# MainSheet.net
KiCad netlist of a schematic drawn in Altium Designer
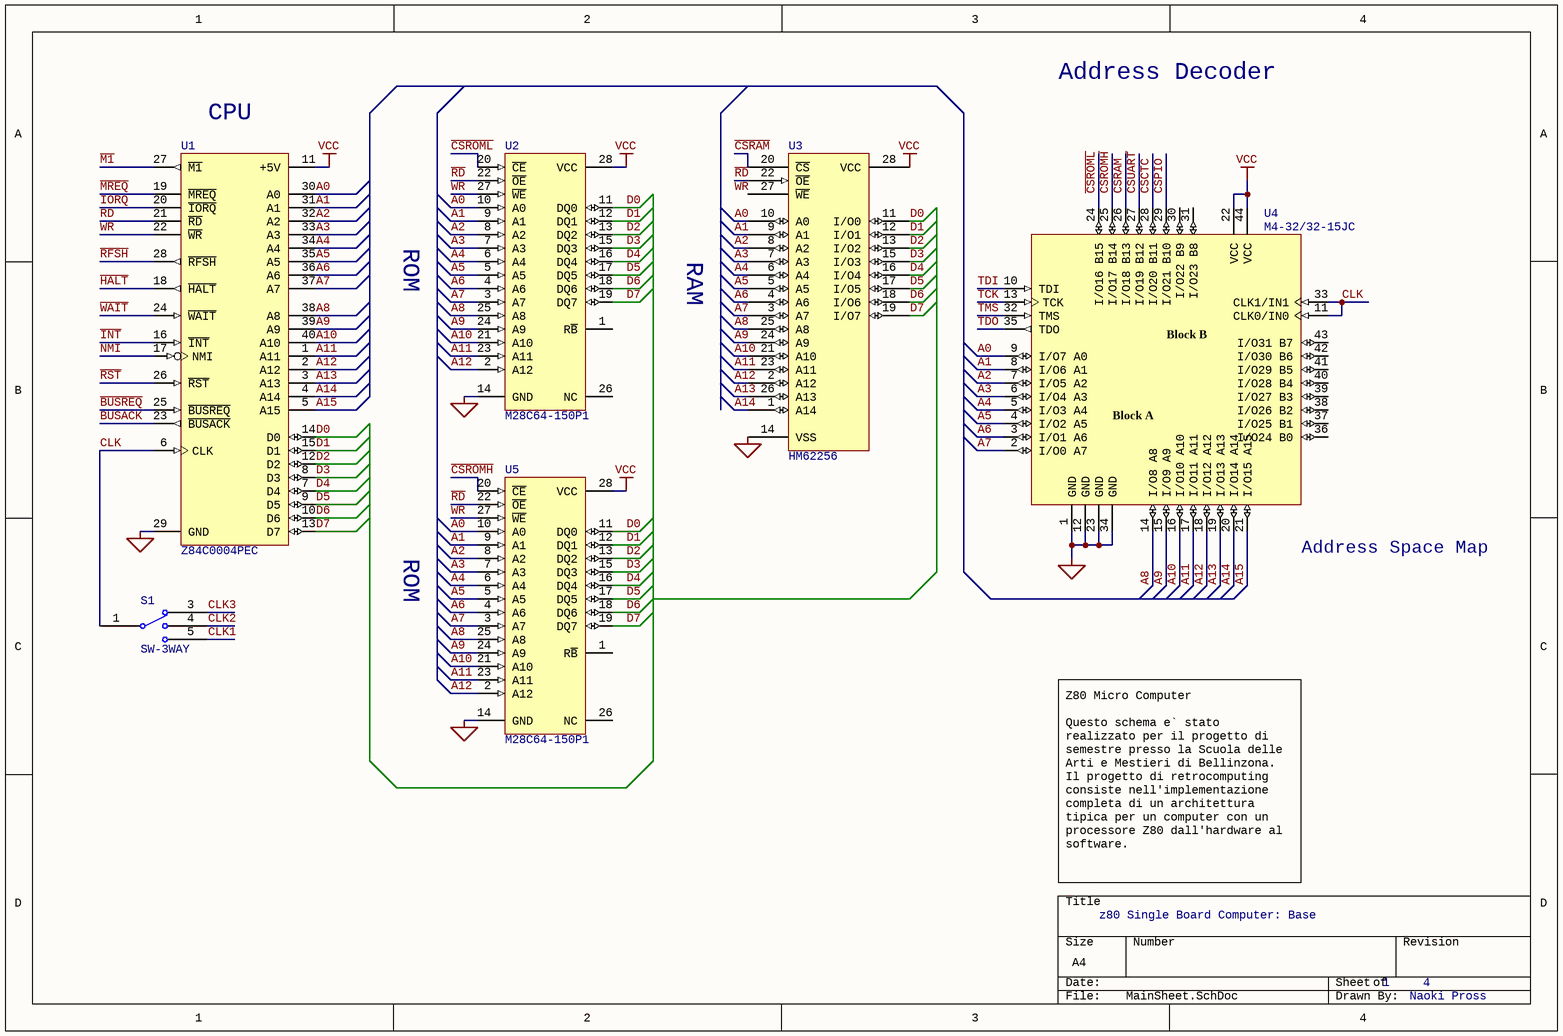
[diagram p0: MainSheet.SchDoc]

(export (version "E")
  (design (tool "Eeschema 10.0.6"))
  (components
    (comp (ref "S1")
      (value "SW-3WAY")
      (description "SGA-13P-03V-7295")
      (libsource (lib "z80uPC") (part "SW-3WAY"))
    )
    (comp (ref "U1")
      (value "Z84C0004PEC")
      (footprint "PDIP40")
      (description "CMOS 8-Bit Microprocessor")
      (fields (field (name "PUBLISHER") "Altium Limited"))
      (libsource (lib "Zilog Microprocessor 8-Bit") (part "Z84C0004PEC"))
    )
    (comp (ref "U2")
      (value "M28C64-150P1")
      (footprint "PDIP28")
      (description "Parallel 64 Kbit (8K x 8) EEPROM with Software Data Protection")
      (fields (field (name "PUBLISHER") "Altium Limited"))
      (libsource (lib "ST Memory EEPROM Parallel") (part "M28C64-150P1"))
    )
    (comp (ref "U3")
      (value "HM62256")
      (footprint "PDIP28")
      (description "8K x 8 Static RAM")
      (libsource (lib "HITACHI Memory Non-Volatile RAM") (part "HM62256"))
    )
    (comp (ref "U4")
      (value "M4-32/32-15JC")
      (footprint "PLCC44_N")
      (description "High-Performance EE CMOS In-System Programmable Logic")
      (fields (field (name "PUBLISHER") "Altium Limited"))
      (libsource (lib "Lattice CPLD ispMACH") (part "M4-32/32-15JC"))
    )
    (comp (ref "U5")
      (value "M28C64-150P1")
      (footprint "PDIP28")
      (description "Parallel 64 Kbit (8K x 8) EEPROM with Software Data Protection")
      (fields (field (name "PUBLISHER") "Altium Limited"))
      (libsource (lib "ST Memory EEPROM Parallel") (part "M28C64-150P1"))
    )
  )
  (nets
    (net (code "1") (name "/A0") (class "Default")
      (node (ref "U1") (pin "30") (pinfunction "A0_30") (pintype "tri_state"))
      (node (ref "U2") (pin "10") (pinfunction "A0_10") (pintype "input"))
      (node (ref "U3") (pin "10") (pinfunction "A0_10") (pintype "bidirectional"))
      (node (ref "U4") (pin "9") (pinfunction "I/O7_A0_9") (pintype "bidirectional"))
      (node (ref "U5") (pin "10") (pinfunction "A0_10") (pintype "input"))
    )
    (net (code "2") (name "/A1") (class "Default")
      (node (ref "U1") (pin "31") (pinfunction "A1_31") (pintype "tri_state"))
      (node (ref "U2") (pin "9") (pinfunction "A1_9") (pintype "input"))
      (node (ref "U3") (pin "9") (pinfunction "A1_9") (pintype "bidirectional"))
      (node (ref "U4") (pin "8") (pinfunction "I/O6_A1_8") (pintype "bidirectional"))
      (node (ref "U5") (pin "9") (pinfunction "A1_9") (pintype "input"))
    )
    (net (code "3") (name "/A2") (class "Default")
      (node (ref "U1") (pin "32") (pinfunction "A2_32") (pintype "tri_state"))
      (node (ref "U2") (pin "8") (pinfunction "A2_8") (pintype "input"))
      (node (ref "U3") (pin "8") (pinfunction "A2_8") (pintype "bidirectional"))
      (node (ref "U4") (pin "7") (pinfunction "I/O5_A2_7") (pintype "bidirectional"))
      (node (ref "U5") (pin "8") (pinfunction "A2_8") (pintype "input"))
    )
    (net (code "4") (name "/A3") (class "Default")
      (node (ref "U1") (pin "33") (pinfunction "A3_33") (pintype "tri_state"))
      (node (ref "U2") (pin "7") (pinfunction "A3_7") (pintype "input"))
      (node (ref "U3") (pin "7") (pinfunction "A3_7") (pintype "bidirectional"))
      (node (ref "U4") (pin "6") (pinfunction "I/O4_A3_6") (pintype "bidirectional"))
      (node (ref "U5") (pin "7") (pinfunction "A3_7") (pintype "input"))
    )
    (net (code "5") (name "/A4") (class "Default")
      (node (ref "U1") (pin "34") (pinfunction "A4_34") (pintype "tri_state"))
      (node (ref "U2") (pin "6") (pinfunction "A4_6") (pintype "input"))
      (node (ref "U3") (pin "6") (pinfunction "A4_6") (pintype "bidirectional"))
      (node (ref "U4") (pin "5") (pinfunction "I/O3_A4_5") (pintype "bidirectional"))
      (node (ref "U5") (pin "6") (pinfunction "A4_6") (pintype "input"))
    )
    (net (code "6") (name "/A5") (class "Default")
      (node (ref "U1") (pin "35") (pinfunction "A5_35") (pintype "tri_state"))
      (node (ref "U2") (pin "5") (pinfunction "A5_5") (pintype "input"))
      (node (ref "U3") (pin "5") (pinfunction "A5_5") (pintype "bidirectional"))
      (node (ref "U4") (pin "4") (pinfunction "I/O2_A5_4") (pintype "bidirectional"))
      (node (ref "U5") (pin "5") (pinfunction "A5_5") (pintype "input"))
    )
    (net (code "7") (name "/A6") (class "Default")
      (node (ref "U1") (pin "36") (pinfunction "A6_36") (pintype "tri_state"))
      (node (ref "U2") (pin "4") (pinfunction "A6_4") (pintype "input"))
      (node (ref "U3") (pin "4") (pinfunction "A6_4") (pintype "bidirectional"))
      (node (ref "U4") (pin "3") (pinfunction "I/O1_A6_3") (pintype "bidirectional"))
      (node (ref "U5") (pin "4") (pinfunction "A6_4") (pintype "input"))
    )
    (net (code "8") (name "/A7") (class "Default")
      (node (ref "U1") (pin "37") (pinfunction "A7_37") (pintype "tri_state"))
      (node (ref "U2") (pin "3") (pinfunction "A7_3") (pintype "input"))
      (node (ref "U3") (pin "3") (pinfunction "A7_3") (pintype "bidirectional"))
      (node (ref "U4") (pin "2") (pinfunction "I/O0_A7_2") (pintype "bidirectional"))
      (node (ref "U5") (pin "3") (pinfunction "A7_3") (pintype "input"))
    )
    (net (code "9") (name "/A8") (class "Default")
      (node (ref "U1") (pin "38") (pinfunction "A8_38") (pintype "tri_state"))
      (node (ref "U2") (pin "25") (pinfunction "A8_25") (pintype "input"))
      (node (ref "U3") (pin "25") (pinfunction "A8_25") (pintype "bidirectional"))
      (node (ref "U4") (pin "14") (pinfunction "I/O8_A8_14") (pintype "bidirectional"))
      (node (ref "U5") (pin "25") (pinfunction "A8_25") (pintype "input"))
    )
    (net (code "10") (name "/A9") (class "Default")
      (node (ref "U1") (pin "39") (pinfunction "A9_39") (pintype "tri_state"))
      (node (ref "U2") (pin "24") (pinfunction "A9_24") (pintype "input"))
      (node (ref "U3") (pin "24") (pinfunction "A9_24") (pintype "bidirectional"))
      (node (ref "U4") (pin "15") (pinfunction "I/O9_A9_15") (pintype "bidirectional"))
      (node (ref "U5") (pin "24") (pinfunction "A9_24") (pintype "input"))
    )
    (net (code "11") (name "/A10") (class "Default")
      (node (ref "U1") (pin "40") (pinfunction "A10_40") (pintype "tri_state"))
      (node (ref "U2") (pin "21") (pinfunction "A10_21") (pintype "input"))
      (node (ref "U3") (pin "21") (pinfunction "A10_21") (pintype "bidirectional"))
      (node (ref "U4") (pin "16") (pinfunction "I/O10_A10_16") (pintype "bidirectional"))
      (node (ref "U5") (pin "21") (pinfunction "A10_21") (pintype "input"))
    )
    (net (code "12") (name "/A11") (class "Default")
      (node (ref "U1") (pin "1") (pinfunction "A11_1") (pintype "tri_state"))
      (node (ref "U2") (pin "23") (pinfunction "A11_23") (pintype "input"))
      (node (ref "U3") (pin "23") (pinfunction "A11_23") (pintype "bidirectional"))
      (node (ref "U4") (pin "17") (pinfunction "I/O11_A11_17") (pintype "bidirectional"))
      (node (ref "U5") (pin "23") (pinfunction "A11_23") (pintype "input"))
    )
    (net (code "13") (name "/A12") (class "Default")
      (node (ref "U1") (pin "2") (pinfunction "A12_2") (pintype "tri_state"))
      (node (ref "U2") (pin "2") (pinfunction "A12_2") (pintype "input"))
      (node (ref "U3") (pin "2") (pinfunction "A12_2") (pintype "bidirectional"))
      (node (ref "U4") (pin "18") (pinfunction "I/O12_A12_18") (pintype "bidirectional"))
      (node (ref "U5") (pin "2") (pinfunction "A12_2") (pintype "input"))
    )
    (net (code "14") (name "/A13") (class "Default")
      (node (ref "U1") (pin "3") (pinfunction "A13_3") (pintype "tri_state"))
      (node (ref "U3") (pin "26") (pinfunction "A13_26") (pintype "bidirectional"))
      (node (ref "U4") (pin "19") (pinfunction "I/O13_A13_19") (pintype "bidirectional"))
    )
    (net (code "15") (name "/A14") (class "Default")
      (node (ref "U1") (pin "4") (pinfunction "A14_4") (pintype "tri_state"))
      (node (ref "U3") (pin "1") (pinfunction "A14_1") (pintype "bidirectional"))
      (node (ref "U4") (pin "20") (pinfunction "I/O14_A14_20") (pintype "bidirectional"))
    )
    (net (code "16") (name "/A15") (class "Default")
      (node (ref "U1") (pin "5") (pinfunction "A15_5") (pintype "tri_state"))
      (node (ref "U4") (pin "21") (pinfunction "I/O15_A15_21") (pintype "bidirectional"))
    )
    (net (code "17") (name "/CLK") (class "Default")
      (node (ref "U1") (pin "6") (pinfunction "CLK_6") (pintype "input"))
      (node (ref "U4") (pin "11") (pinfunction "CLK0/IN0_11") (pintype "input"))
      (node (ref "U4") (pin "33") (pinfunction "CLK1/IN1_33") (pintype "input"))
    )
    (net (code "21") (name "/D0") (class "Default")
      (node (ref "U1") (pin "14") (pinfunction "D0_14") (pintype "bidirectional"))
      (node (ref "U2") (pin "11") (pinfunction "DQ0_11") (pintype "bidirectional"))
      (node (ref "U3") (pin "11") (pinfunction "I/O0_11") (pintype "bidirectional"))
      (node (ref "U5") (pin "11") (pinfunction "DQ0_11") (pintype "bidirectional"))
    )
    (net (code "22") (name "/D1") (class "Default")
      (node (ref "U1") (pin "15") (pinfunction "D1_15") (pintype "bidirectional"))
      (node (ref "U2") (pin "12") (pinfunction "DQ1_12") (pintype "bidirectional"))
      (node (ref "U3") (pin "12") (pinfunction "I/O1_12") (pintype "bidirectional"))
      (node (ref "U5") (pin "12") (pinfunction "DQ1_12") (pintype "bidirectional"))
    )
    (net (code "23") (name "/D2") (class "Default")
      (node (ref "U1") (pin "12") (pinfunction "D2_12") (pintype "bidirectional"))
      (node (ref "U2") (pin "13") (pinfunction "DQ2_13") (pintype "bidirectional"))
      (node (ref "U3") (pin "13") (pinfunction "I/O2_13") (pintype "bidirectional"))
      (node (ref "U5") (pin "13") (pinfunction "DQ2_13") (pintype "bidirectional"))
    )
    (net (code "24") (name "/D3") (class "Default")
      (node (ref "U1") (pin "8") (pinfunction "D3_8") (pintype "bidirectional"))
      (node (ref "U2") (pin "15") (pinfunction "DQ3_15") (pintype "bidirectional"))
      (node (ref "U3") (pin "15") (pinfunction "I/O3_15") (pintype "bidirectional"))
      (node (ref "U5") (pin "15") (pinfunction "DQ3_15") (pintype "bidirectional"))
    )
    (net (code "25") (name "/D4") (class "Default")
      (node (ref "U1") (pin "7") (pinfunction "D4_7") (pintype "bidirectional"))
      (node (ref "U2") (pin "16") (pinfunction "DQ4_16") (pintype "bidirectional"))
      (node (ref "U3") (pin "16") (pinfunction "I/O4_16") (pintype "bidirectional"))
      (node (ref "U5") (pin "16") (pinfunction "DQ4_16") (pintype "bidirectional"))
    )
    (net (code "26") (name "/D5") (class "Default")
      (node (ref "U1") (pin "9") (pinfunction "D5_9") (pintype "bidirectional"))
      (node (ref "U2") (pin "17") (pinfunction "DQ5_17") (pintype "bidirectional"))
      (node (ref "U3") (pin "17") (pinfunction "I/O5_17") (pintype "bidirectional"))
      (node (ref "U5") (pin "17") (pinfunction "DQ5_17") (pintype "bidirectional"))
    )
    (net (code "27") (name "/D6") (class "Default")
      (node (ref "U1") (pin "10") (pinfunction "D6_10") (pintype "bidirectional"))
      (node (ref "U2") (pin "18") (pinfunction "DQ6_18") (pintype "bidirectional"))
      (node (ref "U3") (pin "18") (pinfunction "I/O6_18") (pintype "bidirectional"))
      (node (ref "U5") (pin "18") (pinfunction "DQ6_18") (pintype "bidirectional"))
    )
    (net (code "28") (name "/D7") (class "Default")
      (node (ref "U1") (pin "13") (pinfunction "D7_13") (pintype "bidirectional"))
      (node (ref "U2") (pin "19") (pinfunction "DQ7_19") (pintype "bidirectional"))
      (node (ref "U3") (pin "19") (pinfunction "I/O7_19") (pintype "bidirectional"))
      (node (ref "U5") (pin "19") (pinfunction "DQ7_19") (pintype "bidirectional"))
    )
    (net (code "29") (name "/NMI") (class "Default")
      (node (ref "U1") (pin "17") (pinfunction "NMI_17") (pintype "input"))
    )
    (net (code "30") (name "/TCK") (class "Default")
      (node (ref "U4") (pin "13") (pinfunction "TCK_13") (pintype "input"))
    )
    (net (code "31") (name "/TDI") (class "Default")
      (node (ref "U4") (pin "10") (pinfunction "TDI_10") (pintype "input"))
    )
    (net (code "32") (name "/TDO") (class "Default")
      (node (ref "U4") (pin "35") (pinfunction "TDO_35") (pintype "output"))
    )
    (net (code "33") (name "/TMS") (class "Default")
      (node (ref "U4") (pin "32") (pinfunction "TMS_32") (pintype "input"))
    )
    (net (code "34") (name "/~{BUSACK}") (class "Default")
      (node (ref "U1") (pin "23") (pinfunction "~{BUSACK}_23") (pintype "output"))
    )
    (net (code "35") (name "/~{BUSREQ}") (class "Default")
      (node (ref "U1") (pin "25") (pinfunction "~{BUSREQ}_25") (pintype "input"))
    )
    (net (code "36") (name "/~{CSCTC}") (class "Default")
      (node (ref "U4") (pin "28") (pinfunction "I/O20_B11_28") (pintype "bidirectional"))
    )
    (net (code "37") (name "/~{CSPIO}") (class "Default")
      (node (ref "U4") (pin "29") (pinfunction "I/O21_B10_29") (pintype "bidirectional"))
    )
    (net (code "38") (name "/~{CSRAM}") (class "Default")
      (node (ref "U3") (pin "20") (pinfunction "~{CS}_20") (pintype "passive"))
      (node (ref "U4") (pin "26") (pinfunction "I/O18_B13_26") (pintype "bidirectional"))
    )
    (net (code "39") (name "/~{CSROMH}") (class "Default")
      (node (ref "U4") (pin "25") (pinfunction "I/O17_B14_25") (pintype "bidirectional"))
      (node (ref "U5") (pin "20") (pinfunction "~{CE}_20") (pintype "input"))
    )
    (net (code "40") (name "/~{CSROML}") (class "Default")
      (node (ref "U2") (pin "20") (pinfunction "~{CE}_20") (pintype "input"))
      (node (ref "U4") (pin "24") (pinfunction "I/O16_B15_24") (pintype "bidirectional"))
    )
    (net (code "41") (name "/~{CSUART}") (class "Default")
      (node (ref "U4") (pin "27") (pinfunction "I/O19_B12_27") (pintype "bidirectional"))
    )
    (net (code "42") (name "/~{HALT}") (class "Default")
      (node (ref "U1") (pin "18") (pinfunction "~{HALT}_18") (pintype "output"))
    )
    (net (code "43") (name "/~{INT}") (class "Default")
      (node (ref "U1") (pin "16") (pinfunction "~{INT}_16") (pintype "input"))
    )
    (net (code "44") (name "/~{IORQ}") (class "Default")
      (node (ref "U1") (pin "20") (pinfunction "~{IORQ}_20") (pintype "tri_state"))
    )
    (net (code "45") (name "/~{M1}") (class "Default")
      (node (ref "U1") (pin "27") (pinfunction "~{M1}_27") (pintype "output"))
    )
    (net (code "46") (name "/~{MREQ}") (class "Default")
      (node (ref "U1") (pin "19") (pinfunction "~{MREQ}_19") (pintype "tri_state"))
    )
    (net (code "47") (name "/~{RD}") (class "Default")
      (node (ref "U1") (pin "21") (pinfunction "~{RD}_21") (pintype "tri_state"))
      (node (ref "U2") (pin "22") (pinfunction "~{OE}_22") (pintype "input"))
      (node (ref "U3") (pin "22") (pinfunction "~{OE}_22") (pintype "input"))
      (node (ref "U5") (pin "22") (pinfunction "~{OE}_22") (pintype "input"))
    )
    (net (code "48") (name "/~{RFSH}") (class "Default")
      (node (ref "U1") (pin "28") (pinfunction "~{RFSH}_28") (pintype "output"))
    )
    (net (code "49") (name "/~{RST}") (class "Default")
      (node (ref "U1") (pin "26") (pinfunction "~{RST}_26") (pintype "input"))
    )
    (net (code "50") (name "/~{WAIT}") (class "Default")
      (node (ref "U1") (pin "24") (pinfunction "~{WAIT}_24") (pintype "input"))
    )
    (net (code "51") (name "/~{WR}") (class "Default")
      (node (ref "U1") (pin "22") (pinfunction "~{WR}_22") (pintype "tri_state"))
      (node (ref "U2") (pin "27") (pinfunction "~{WE}_27") (pintype "input"))
      (node (ref "U5") (pin "27") (pinfunction "~{WE}_27") (pintype "input"))
    )
    (net (code "52") (name "GND") (class "Default")
      (node (ref "U1") (pin "29") (pinfunction "GND_29") (pintype "power_in"))
      (node (ref "U2") (pin "14") (pinfunction "GND_14") (pintype "power_in"))
      (node (ref "U3") (pin "14") (pinfunction "VSS_14") (pintype "power_in"))
      (node (ref "U4") (pin "1") (pinfunction "GND_1") (pintype "power_in"))
      (node (ref "U4") (pin "12") (pinfunction "GND_12") (pintype "power_in"))
      (node (ref "U4") (pin "23") (pinfunction "GND_23") (pintype "power_in"))
      (node (ref "U4") (pin "34") (pinfunction "GND_34") (pintype "power_in"))
      (node (ref "U5") (pin "14") (pinfunction "GND_14") (pintype "power_in"))
    )
    (net (code "53") (name "VCC") (class "Default")
      (node (ref "U1") (pin "11") (pinfunction "+5V_11") (pintype "power_in"))
      (node (ref "U2") (pin "28") (pinfunction "VCC_28") (pintype "power_in"))
      (node (ref "U3") (pin "28") (pinfunction "VCC_28") (pintype "power_in"))
      (node (ref "U4") (pin "22") (pinfunction "VCC_22") (pintype "power_in"))
      (node (ref "U4") (pin "44") (pinfunction "VCC_44") (pintype "power_in"))
      (node (ref "U5") (pin "28") (pinfunction "VCC_28") (pintype "power_in"))
    )
    (net (code "54") (name "unconnected-(S1-Pad1)") (class "Default")
      (node (ref "S1") (pin "1") (pintype "passive"))
    )
    (net (code "55") (name "unconnected-(S1-Pad3)") (class "Default")
      (node (ref "S1") (pin "3") (pintype "passive"))
    )
    (net (code "56") (name "unconnected-(S1-Pad4)") (class "Default")
      (node (ref "S1") (pin "4") (pintype "passive"))
    )
    (net (code "57") (name "unconnected-(S1-Pad5)") (class "Default")
      (node (ref "S1") (pin "5") (pintype "passive"))
    )
    (net (code "58") (name "unconnected-(U2-NC-Pad26)") (class "Default")
      (node (ref "U2") (pin "26") (pinfunction "NC_26") (pintype "passive"))
    )
    (net (code "59") (name "unconnected-(U2-R~{B}-Pad1)") (class "Default")
      (node (ref "U2") (pin "1") (pinfunction "R~{B}_1") (pintype "passive"))
    )
    (net (code "60") (name "unconnected-(U3-~{WE}-Pad27)") (class "Default")
      (node (ref "U3") (pin "27") (pinfunction "~{WE}_27") (pintype "passive"))
    )
    (net (code "61") (name "unconnected-(U4-I{slash}O22_B9-Pad30)") (class "Default")
      (node (ref "U4") (pin "30") (pinfunction "I/O22_B9_30") (pintype "bidirectional"))
    )
    (net (code "62") (name "unconnected-(U4-I{slash}O23_B8-Pad31)") (class "Default")
      (node (ref "U4") (pin "31") (pinfunction "I/O23_B8_31") (pintype "bidirectional"))
    )
    (net (code "63") (name "unconnected-(U4-I{slash}O24_B0-Pad36)") (class "Default")
      (node (ref "U4") (pin "36") (pinfunction "I/O24_B0_36") (pintype "bidirectional"))
    )
    (net (code "64") (name "unconnected-(U4-I{slash}O25_B1-Pad37)") (class "Default")
      (node (ref "U4") (pin "37") (pinfunction "I/O25_B1_37") (pintype "bidirectional"))
    )
    (net (code "65") (name "unconnected-(U4-I{slash}O26_B2-Pad38)") (class "Default")
      (node (ref "U4") (pin "38") (pinfunction "I/O26_B2_38") (pintype "bidirectional"))
    )
    (net (code "66") (name "unconnected-(U4-I{slash}O27_B3-Pad39)") (class "Default")
      (node (ref "U4") (pin "39") (pinfunction "I/O27_B3_39") (pintype "bidirectional"))
    )
    (net (code "67") (name "unconnected-(U4-I{slash}O28_B4-Pad40)") (class "Default")
      (node (ref "U4") (pin "40") (pinfunction "I/O28_B4_40") (pintype "bidirectional"))
    )
    (net (code "68") (name "unconnected-(U4-I{slash}O29_B5-Pad41)") (class "Default")
      (node (ref "U4") (pin "41") (pinfunction "I/O29_B5_41") (pintype "bidirectional"))
    )
    (net (code "69") (name "unconnected-(U4-I{slash}O30_B6-Pad42)") (class "Default")
      (node (ref "U4") (pin "42") (pinfunction "I/O30_B6_42") (pintype "bidirectional"))
    )
    (net (code "70") (name "unconnected-(U4-I{slash}O31_B7-Pad43)") (class "Default")
      (node (ref "U4") (pin "43") (pinfunction "I/O31_B7_43") (pintype "bidirectional"))
    )
    (net (code "71") (name "unconnected-(U5-NC-Pad26)") (class "Default")
      (node (ref "U5") (pin "26") (pinfunction "NC_26") (pintype "passive"))
    )
    (net (code "72") (name "unconnected-(U5-R~{B}-Pad1)") (class "Default")
      (node (ref "U5") (pin "1") (pinfunction "R~{B}_1") (pintype "passive"))
    )
  )
)
